# Template_Sensor_schematic.net
KiCad netlist of a schematic drawn in Altium Designer
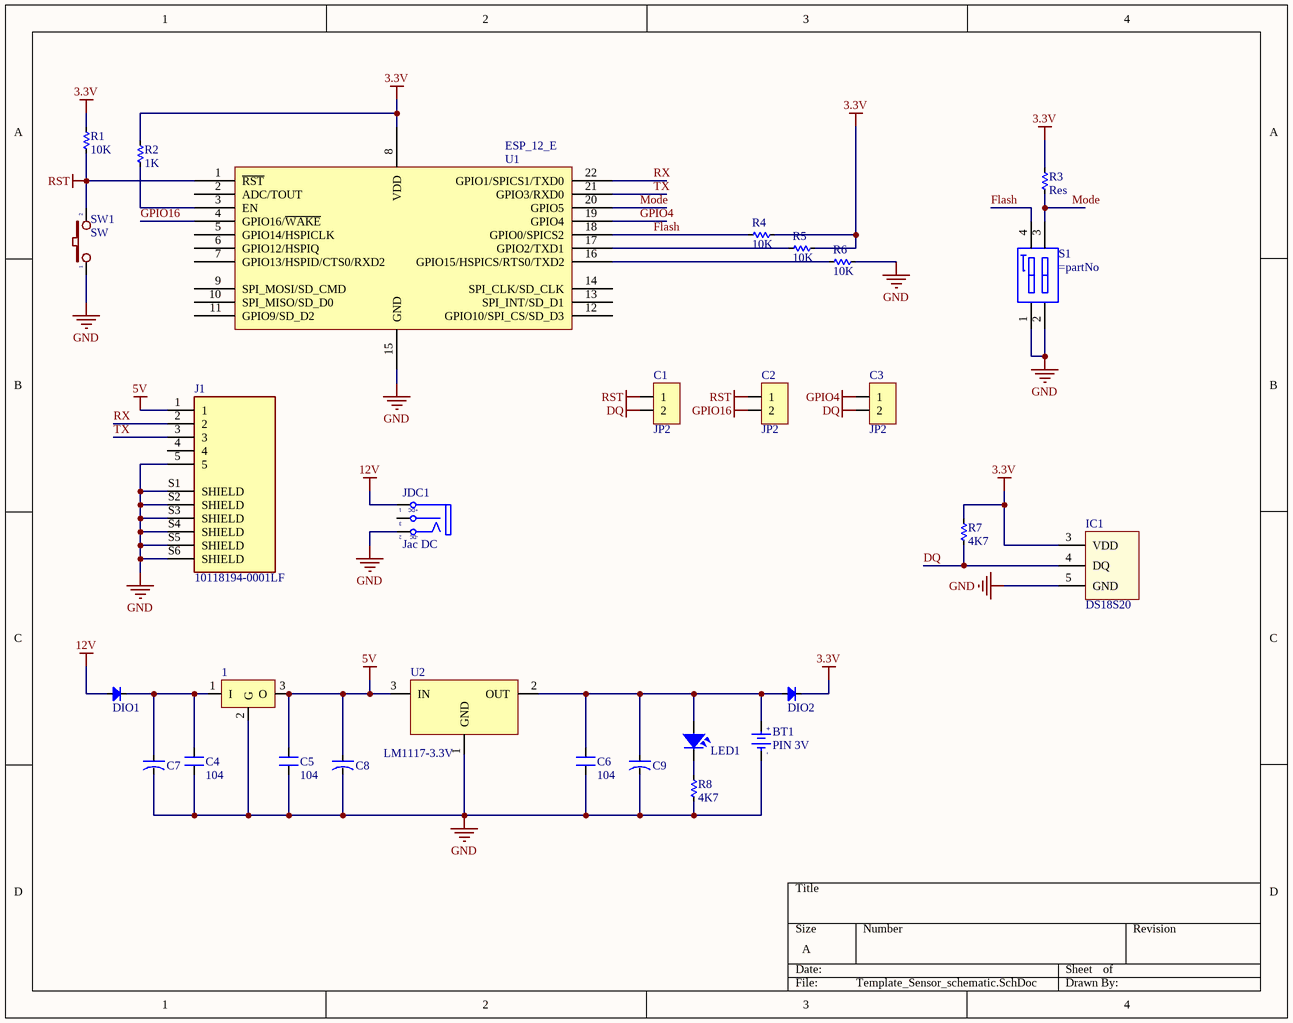
[diagram p0: Template_Sensor_schematic.SchDoc]

(export (version "E")
  (design (tool "Eeschema 10.0.6"))
  (components
    (comp (ref "1")
      (value "LM78xx")
      (footprint "TO252-123")
      (description "Positive Voltage Regulator")
      (fields (field (name "PUBLISHER") "Altium Limited"))
      (libsource (lib "LIBRARY") (part "LM78xx"))
    )
    (comp (ref "BT1")
      (value "PIN 3V")
      (footprint "PIN3V")
      (description "Battery 3VDC")
      (libsource (lib "LIBRARY") (part "PIN 3V"))
    )
    (comp (ref "C1")
      (value "JP2")
      (footprint "JP2-D1T")
      (description "WR-PHD 2.54 mm Angled Socket Header")
      (fields
        (field (name "MANUFACTURER") "Würth Elektronik eiSos GmbH")
        (field (name "PARTNO") "613002143121")
        (field (name "CREATED BY") "Karrer Zheng")
      )
      (libsource (lib "LIBRARY") (part "JP2"))
    )
    (comp (ref "C2")
      (value "JP2")
      (footprint "JP2-D1T")
      (description "WR-PHD 2.54 mm Angled Socket Header")
      (fields
        (field (name "MANUFACTURER") "Würth Elektronik eiSos GmbH")
        (field (name "PARTNO") "613002143121")
        (field (name "CREATED BY") "Karrer Zheng")
      )
      (libsource (lib "LIBRARY") (part "JP2"))
    )
    (comp (ref "C3")
      (value "JP2")
      (footprint "JP2-D1T")
      (description "WR-PHD 2.54 mm Angled Socket Header")
      (fields
        (field (name "MANUFACTURER") "Würth Elektronik eiSos GmbH")
        (field (name "PARTNO") "613002143121")
        (field (name "CREATED BY") "Karrer Zheng")
      )
      (libsource (lib "LIBRARY") (part "JP2"))
    )
    (comp (ref "C4")
      (value "104")
      (footprint "SM-CAP-0805")
      (fields (field (name "DESIGNED BY") "VanDungEvn"))
      (libsource (lib "electronicvn-library1") (part "CN"))
    )
    (comp (ref "C5")
      (value "104")
      (footprint "SM-CAP-0805")
      (fields (field (name "DESIGNED BY") "VanDungEvn"))
      (libsource (lib "electronicvn-library1") (part "CN"))
    )
    (comp (ref "C6")
      (value "104")
      (footprint "SM-CAP-0805")
      (fields (field (name "DESIGNED BY") "VanDungEvn"))
      (libsource (lib "electronicvn-library1") (part "CN"))
    )
    (comp (ref "C7")
      (value "CN-ALU-SMD")
      (footprint "CAP-ALU-SMD-4.5x5x1.4")
      (description "Polarized Capacitor (Axial)")
      (fields (field (name "PUBLISHER") "Altium Limited"))
      (libsource (lib "LIBTanCN") (part "CN-ALU-SMD"))
    )
    (comp (ref "C8")
      (value "CN-ALU-SMD")
      (footprint "CAP-ALU-SMD-4.5x5x1.4")
      (description "Polarized Capacitor (Axial)")
      (fields (field (name "PUBLISHER") "Altium Limited"))
      (libsource (lib "LIBTanCN") (part "CN-ALU-SMD"))
    )
    (comp (ref "C9")
      (value "CN-ALU-SMD")
      (footprint "CAP-ALU-SMD-4.5x5x1.4")
      (description "Polarized Capacitor (Axial)")
      (fields (field (name "PUBLISHER") "Altium Limited"))
      (libsource (lib "LIBTanCN") (part "CN-ALU-SMD"))
    )
    (comp (ref "DIO1")
      (value "Diode SMD")
      (footprint "DIO-SMD-106")
      (description "Default Diode")
      (fields (field (name "PUBLISHER") "Altium Limited"))
      (libsource (lib "LIBRARY") (part "Diode SMD"))
    )
    (comp (ref "DIO2")
      (value "Diode SMD")
      (footprint "DIO-SMD-106")
      (description "Default Diode")
      (fields (field (name "PUBLISHER") "Altium Limited"))
      (libsource (lib "LIBRARY") (part "Diode SMD"))
    )
    (comp (ref "IC1")
      (value "DS18S20")
      (footprint "DS18S20")
      (description "High Precision  1-Wire® Digital Thermometer")
      (libsource (lib "LIBTanCN") (part "DS18S20"))
    )
    (comp (ref "J1")
      (value "10118194-0001LF")
      (footprint "AMPHENOL_10118194-0001LF")
      (description "USB - micro B USB 2.0 Receptacle Connector 5 Position Surface Mount, Right Angle; Through Hole")
      (fields (field (name "MF") "Amphenol ICC"))
      (libsource (lib "10118194-0001LF") (part "10118194-0001LF"))
    )
    (comp (ref "JDC1")
      (value "Jac DC")
      (footprint "DC3")
      (description "Jac DC input")
      (libsource (lib "LIBRARY") (part "DCIN"))
    )
    (comp (ref "LED1") (value "LED") (footprint "LED-0805-Blue") (libsource (lib "LIBRARY") (part "LED SMD")))
    (comp (ref "R1")
      (value "10K")
      (footprint "RES-SMD-0805")
      (description "Resistor")
      (fields
        (field (name "MANUFACTURER") "Generic Components")
        (field (name "PUBLISHER") "Altium Hobart Technology Centre")
      )
      (libsource (lib "LIBRARY") (part "Res-SMD"))
    )
    (comp (ref "R2")
      (value "1K")
      (footprint "RES-SMD-0805")
      (description "Resistor")
      (fields
        (field (name "MANUFACTURER") "Generic Components")
        (field (name "PUBLISHER") "Altium Hobart Technology Centre")
      )
      (libsource (lib "LIBRARY") (part "Res-SMD"))
    )
    (comp (ref "R3")
      (value "Res")
      (footprint "RES-SMD-0805")
      (description "Resistor")
      (fields
        (field (name "MANUFACTURER") "Generic Components")
        (field (name "PUBLISHER") "Altium Hobart Technology Centre")
      )
      (libsource (lib "LIBRARY") (part "Res-SMD"))
    )
    (comp (ref "R4")
      (value "10K")
      (footprint "RES-SMD-0805")
      (description "Resistor")
      (fields
        (field (name "MANUFACTURER") "Generic Components")
        (field (name "PUBLISHER") "Altium Hobart Technology Centre")
      )
      (libsource (lib "LIBRARY") (part "Res-SMD"))
    )
    (comp (ref "R5")
      (value "10K")
      (footprint "RES-SMD-0805")
      (description "Resistor")
      (fields
        (field (name "MANUFACTURER") "Generic Components")
        (field (name "PUBLISHER") "Altium Hobart Technology Centre")
      )
      (libsource (lib "LIBRARY") (part "Res-SMD"))
    )
    (comp (ref "R6")
      (value "10K")
      (footprint "RES-SMD-0805")
      (description "Resistor")
      (fields
        (field (name "MANUFACTURER") "Generic Components")
        (field (name "PUBLISHER") "Altium Hobart Technology Centre")
      )
      (libsource (lib "LIBRARY") (part "Res-SMD"))
    )
    (comp (ref "R7")
      (value "4K7")
      (footprint "RES-SMD-0805")
      (description "Resistor")
      (fields
        (field (name "MANUFACTURER") "Generic Components")
        (field (name "PUBLISHER") "Altium Hobart Technology Centre")
      )
      (libsource (lib "LIBRARY") (part "Res-SMD"))
    )
    (comp (ref "R8")
      (value "4K7")
      (footprint "RES-SMD-0805")
      (description "Resistor")
      (fields
        (field (name "MANUFACTURER") "Generic Components")
        (field (name "PUBLISHER") "Altium Hobart Technology Centre")
      )
      (libsource (lib "LIBRARY") (part "Res-SMD"))
    )
    (comp (ref "S1")
      (value "~")
      (footprint "SW-DIP2")
      (description "WS-DITV 2.54 mm small compact THT flat actuator with top tape")
      (fields
        (field (name "MANUFACTURER") "Wurth Elektronik")
        (field (name "PART NO.") "418127160902")
        (field (name "CREATED BY") "Baojun Chen")
      )
      (libsource (lib "LIBRARY") (part "SWDIP2"))
    )
    (comp (ref "SW1")
      (value "SW")
      (footprint "SW1-SMD")
      (description "Switch button 2 pin")
      (libsource (lib "LIBRARY") (part "SW2"))
    )
    (comp (ref "U1")
      (value "ESP_12_E")
      (footprint "ESP_12_E")
      (description "ESP-12 Wi-Fi Module by AI-Thinker")
      (libsource (lib "ESP8266") (part "ESP_12_E"))
    )
    (comp (ref "U2")
      (value "LM1117-3.3V")
      (footprint "SOT223")
      (description "800mA Low-Dropout Linear Regulator")
      (fields (field (name "CREATOR") "Nguyen Ba Bien"))
      (libsource (lib "LIBRARY") (part "LM1117"))
    )
  )
  (nets
    (net (code "1") (name "/Flash") (class "Default")
      (node (ref "R4") (pin "2") (pinfunction "2_2") (pintype "passive"))
      (node (ref "S1") (pin "4") (pinfunction "4_4") (pintype "passive"))
      (node (ref "U1") (pin "18") (pinfunction "GPIO0/SPICS2_18") (pintype "passive"))
    )
    (net (code "2") (name "/Mode") (class "Default")
      (node (ref "R3") (pin "2") (pinfunction "2_2") (pintype "passive"))
      (node (ref "S1") (pin "3") (pinfunction "3_3") (pintype "passive"))
      (node (ref "U1") (pin "20") (pinfunction "GPIO5_20") (pintype "passive"))
    )
    (net (code "3") (name "/RX") (class "Default")
      (node (ref "J1") (pin "2") (pinfunction "2_2") (pintype "passive"))
      (node (ref "U1") (pin "22") (pinfunction "GPIO1/SPICS1/TXD0_22") (pintype "passive"))
    )
    (net (code "4") (name "/TX") (class "Default")
      (node (ref "J1") (pin "3") (pinfunction "3_3") (pintype "passive"))
      (node (ref "U1") (pin "21") (pinfunction "GPIO3/RXD0_21") (pintype "passive"))
    )
    (net (code "5") (name "3.3V") (class "Default")
      (node (ref "DIO2") (pin "2") (pinfunction "K_2") (pintype "passive"))
      (node (ref "IC1") (pin "3") (pinfunction "VDD_3") (pintype "passive"))
      (node (ref "R1") (pin "1") (pinfunction "1_1") (pintype "passive"))
      (node (ref "R2") (pin "1") (pinfunction "1_1") (pintype "passive"))
      (node (ref "R3") (pin "1") (pinfunction "1_1") (pintype "passive"))
      (node (ref "R4") (pin "1") (pinfunction "1_1") (pintype "passive"))
      (node (ref "R5") (pin "1") (pinfunction "1_1") (pintype "passive"))
      (node (ref "R7") (pin "1") (pinfunction "1_1") (pintype "passive"))
      (node (ref "U1") (pin "8") (pinfunction "VDD_8") (pintype "passive"))
    )
    (net (code "6") (name "5V") (class "Default")
      (node (ref "1") (pin "3") (pinfunction "O_3") (pintype "power_in"))
      (node (ref "C5") (pin "2") (pinfunction "2_2") (pintype "passive"))
      (node (ref "C8") (pin "1") (pinfunction "1_1") (pintype "passive"))
      (node (ref "J1") (pin "1") (pinfunction "1_1") (pintype "passive"))
      (node (ref "U2") (pin "3") (pinfunction "IN_3") (pintype "passive"))
    )
    (net (code "7") (name "12V") (class "Default")
      (node (ref "DIO1") (pin "1") (pinfunction "A_1") (pintype "passive"))
      (node (ref "JDC1") (pin "1") (pinfunction "T_1") (pintype "passive"))
    )
    (net (code "8") (name "DQ") (class "Default")
      (node (ref "C1") (pin "2") (pinfunction "2_2") (pintype "passive"))
      (node (ref "C3") (pin "2") (pinfunction "2_2") (pintype "passive"))
      (node (ref "IC1") (pin "4") (pinfunction "DQ_4") (pintype "passive"))
      (node (ref "R7") (pin "2") (pinfunction "2_2") (pintype "passive"))
    )
    (net (code "9") (name "GND") (class "Default")
      (node (ref "1") (pin "2") (pinfunction "G_2") (pintype "power_in"))
      (node (ref "BT1") (pin "2") (pinfunction "GND_2") (pintype "passive"))
      (node (ref "C4") (pin "1") (pinfunction "1_1") (pintype "passive"))
      (node (ref "C5") (pin "1") (pinfunction "1_1") (pintype "passive"))
      (node (ref "C6") (pin "1") (pinfunction "1_1") (pintype "passive"))
      (node (ref "C7") (pin "2") (pinfunction "2_2") (pintype "passive"))
      (node (ref "C8") (pin "2") (pinfunction "2_2") (pintype "passive"))
      (node (ref "C9") (pin "2") (pinfunction "2_2") (pintype "passive"))
      (node (ref "IC1") (pin "5") (pinfunction "GND_5") (pintype "passive"))
      (node (ref "J1") (pin "5") (pinfunction "5_5") (pintype "passive"))
      (node (ref "J1") (pin "S1") (pinfunction "SHIELD_S1") (pintype "passive"))
      (node (ref "J1") (pin "S2") (pinfunction "SHIELD_S2") (pintype "passive"))
      (node (ref "J1") (pin "S3") (pinfunction "SHIELD_S3") (pintype "passive"))
      (node (ref "J1") (pin "S4") (pinfunction "SHIELD_S4") (pintype "passive"))
      (node (ref "J1") (pin "S5") (pinfunction "SHIELD_S5") (pintype "passive"))
      (node (ref "J1") (pin "S6") (pinfunction "SHIELD_S6") (pintype "passive"))
      (node (ref "JDC1") (pin "2") (pinfunction "TN_2") (pintype "passive"))
      (node (ref "R6") (pin "1") (pinfunction "1_1") (pintype "passive"))
      (node (ref "R8") (pin "2") (pinfunction "2_2") (pintype "passive"))
      (node (ref "S1") (pin "1") (pinfunction "1_1") (pintype "passive"))
      (node (ref "S1") (pin "2") (pinfunction "2_2") (pintype "passive"))
      (node (ref "SW1") (pin "1") (pinfunction "1_1") (pintype "passive"))
      (node (ref "U1") (pin "15") (pinfunction "GND_15") (pintype "passive"))
      (node (ref "U2") (pin "1") (pinfunction "GND_1") (pintype "passive"))
    )
    (net (code "10") (name "GPIO4") (class "Default")
      (node (ref "C3") (pin "1") (pinfunction "1_1") (pintype "passive"))
      (node (ref "U1") (pin "19") (pinfunction "GPIO4_19") (pintype "passive"))
    )
    (net (code "11") (name "GPIO16") (class "Default")
      (node (ref "C2") (pin "2") (pinfunction "2_2") (pintype "passive"))
      (node (ref "U1") (pin "4") (pinfunction "GPIO16/~{WAKE}_4") (pintype "passive"))
    )
    (net (code "12") (name "Net-(1-I)") (class "Default")
      (node (ref "1") (pin "1") (pinfunction "I_1") (pintype "power_in"))
      (node (ref "C4") (pin "2") (pinfunction "2_2") (pintype "passive"))
      (node (ref "C7") (pin "1") (pinfunction "1_1") (pintype "passive"))
      (node (ref "DIO1") (pin "2") (pinfunction "K_2") (pintype "passive"))
    )
    (net (code "13") (name "Net-(BT1-+3V)") (class "Default")
      (node (ref "BT1") (pin "1") (pinfunction "+3V_1") (pintype "passive"))
      (node (ref "C6") (pin "2") (pinfunction "2_2") (pintype "passive"))
      (node (ref "C9") (pin "1") (pinfunction "1_1") (pintype "passive"))
      (node (ref "DIO2") (pin "1") (pinfunction "A_1") (pintype "passive"))
      (node (ref "LED1") (pin "1") (pinfunction "1_1") (pintype "passive"))
      (node (ref "U2") (pin "2") (pinfunction "OUT_2") (pintype "passive"))
    )
    (net (code "14") (name "Net-(LED1-Pad2)") (class "Default")
      (node (ref "LED1") (pin "2") (pinfunction "2_2") (pintype "passive"))
      (node (ref "R8") (pin "1") (pinfunction "1_1") (pintype "passive"))
    )
    (net (code "15") (name "Net-(U1-EN)") (class "Default")
      (node (ref "R2") (pin "2") (pinfunction "2_2") (pintype "passive"))
      (node (ref "U1") (pin "3") (pinfunction "EN_3") (pintype "passive"))
    )
    (net (code "16") (name "Net-(U1-GPIO2{slash}TXD1)") (class "Default")
      (node (ref "R5") (pin "2") (pinfunction "2_2") (pintype "passive"))
      (node (ref "U1") (pin "17") (pinfunction "GPIO2/TXD1_17") (pintype "passive"))
    )
    (net (code "17") (name "Net-(U1-GPIO15{slash}HSPICS{slash}RTS0{slash}TXD2)") (class "Default")
      (node (ref "R6") (pin "2") (pinfunction "2_2") (pintype "passive"))
      (node (ref "U1") (pin "16") (pinfunction "GPIO15/HSPICS/RTS0/TXD2_16") (pintype "passive"))
    )
    (net (code "18") (name "RST") (class "Default")
      (node (ref "C1") (pin "1") (pinfunction "1_1") (pintype "passive"))
      (node (ref "C2") (pin "1") (pinfunction "1_1") (pintype "passive"))
      (node (ref "R1") (pin "2") (pinfunction "2_2") (pintype "passive"))
      (node (ref "SW1") (pin "2") (pinfunction "2_2") (pintype "passive"))
      (node (ref "U1") (pin "1") (pinfunction "~{RST}_1") (pintype "passive"))
    )
    (net (code "19") (name "unconnected-(J1-Pad4)") (class "Default")
      (node (ref "J1") (pin "4") (pinfunction "4_4") (pintype "passive"))
    )
    (net (code "20") (name "unconnected-(JDC1-S-Pad3)") (class "Default")
      (node (ref "JDC1") (pin "3") (pinfunction "S_3") (pintype "power_in"))
    )
    (net (code "21") (name "unconnected-(U1-ADC{slash}TOUT-Pad2)") (class "Default")
      (node (ref "U1") (pin "2") (pinfunction "ADC/TOUT_2") (pintype "passive"))
    )
    (net (code "22") (name "unconnected-(U1-GPIO9{slash}SD_D2-Pad11)") (class "Default")
      (node (ref "U1") (pin "11") (pinfunction "GPIO9/SD_D2_11") (pintype "passive"))
    )
    (net (code "23") (name "unconnected-(U1-GPIO10{slash}SPI_CS{slash}SD_D3-Pad12)") (class "Default")
      (node (ref "U1") (pin "12") (pinfunction "GPIO10/SPI_CS/SD_D3_12") (pintype "passive"))
    )
    (net (code "24") (name "unconnected-(U1-GPIO12{slash}HSPIQ-Pad6)") (class "Default")
      (node (ref "U1") (pin "6") (pinfunction "GPIO12/HSPIQ_6") (pintype "passive"))
    )
    (net (code "25") (name "unconnected-(U1-GPIO13{slash}HSPID{slash}CTS0{slash}RXD2-Pad7)") (class "Default")
      (node (ref "U1") (pin "7") (pinfunction "GPIO13/HSPID/CTS0/RXD2_7") (pintype "passive"))
    )
    (net (code "26") (name "unconnected-(U1-GPIO14{slash}HSPICLK-Pad5)") (class "Default")
      (node (ref "U1") (pin "5") (pinfunction "GPIO14/HSPICLK_5") (pintype "passive"))
    )
    (net (code "27") (name "unconnected-(U1-SPI_CLK{slash}SD_CLK-Pad14)") (class "Default")
      (node (ref "U1") (pin "14") (pinfunction "SPI_CLK/SD_CLK_14") (pintype "passive"))
    )
    (net (code "28") (name "unconnected-(U1-SPI_INT{slash}SD_D1-Pad13)") (class "Default")
      (node (ref "U1") (pin "13") (pinfunction "SPI_INT/SD_D1_13") (pintype "passive"))
    )
    (net (code "29") (name "unconnected-(U1-SPI_MISO{slash}SD_D0-Pad10)") (class "Default")
      (node (ref "U1") (pin "10") (pinfunction "SPI_MISO/SD_D0_10") (pintype "passive"))
    )
    (net (code "30") (name "unconnected-(U1-SPI_MOSI{slash}SD_CMD-Pad9)") (class "Default")
      (node (ref "U1") (pin "9") (pinfunction "SPI_MOSI/SD_CMD_9") (pintype "passive"))
    )
  )
)
